# spi_flash.net
KiCad netlist of a schematic drawn in Altium Designer
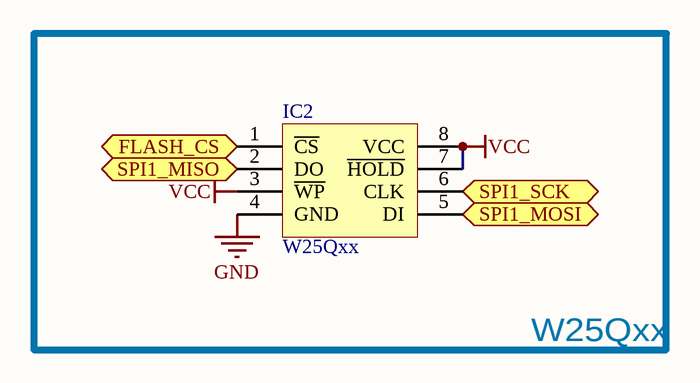
[diagram p0: spi_flash.SchDoc]

(export (version "E")
  (design (tool "Eeschema 10.0.6"))
  (components
    (comp (ref "IC2")
      (value "W25Qxx")
      (footprint "SOP8W_N")
      (description "外置Flash")
      (fields (field (name "版权归属") "源创客"))
      (libsource (lib "1.1   - IC芯片") (part "W25Qxx"))
    )
  )
  (nets
    (net (code "1") (name "/FLASH_CS") (class "Default")
      (node (ref "IC2") (pin "1") (pinfunction "~{CS}_1") (pintype "passive"))
    )
    (net (code "2") (name "/SPI1_MISO") (class "Default")
      (node (ref "IC2") (pin "2") (pinfunction "DO_2") (pintype "passive"))
    )
    (net (code "3") (name "/SPI1_MOSI") (class "Default")
      (node (ref "IC2") (pin "5") (pinfunction "DI_5") (pintype "passive"))
    )
    (net (code "4") (name "/SPI1_SCK") (class "Default")
      (node (ref "IC2") (pin "6") (pinfunction "CLK_6") (pintype "passive"))
    )
    (net (code "5") (name "GND") (class "Default")
      (node (ref "IC2") (pin "4") (pinfunction "GND_4") (pintype "passive"))
    )
    (net (code "6") (name "VCC") (class "Default")
      (node (ref "IC2") (pin "3") (pinfunction "~{WP}_3") (pintype "passive"))
      (node (ref "IC2") (pin "7") (pinfunction "~{HOLD}_7") (pintype "passive"))
      (node (ref "IC2") (pin "8") (pinfunction "VCC_8") (pintype "passive"))
    )
  )
)
